# 18.net
KiCad netlist of a schematic drawn in Altium Designer
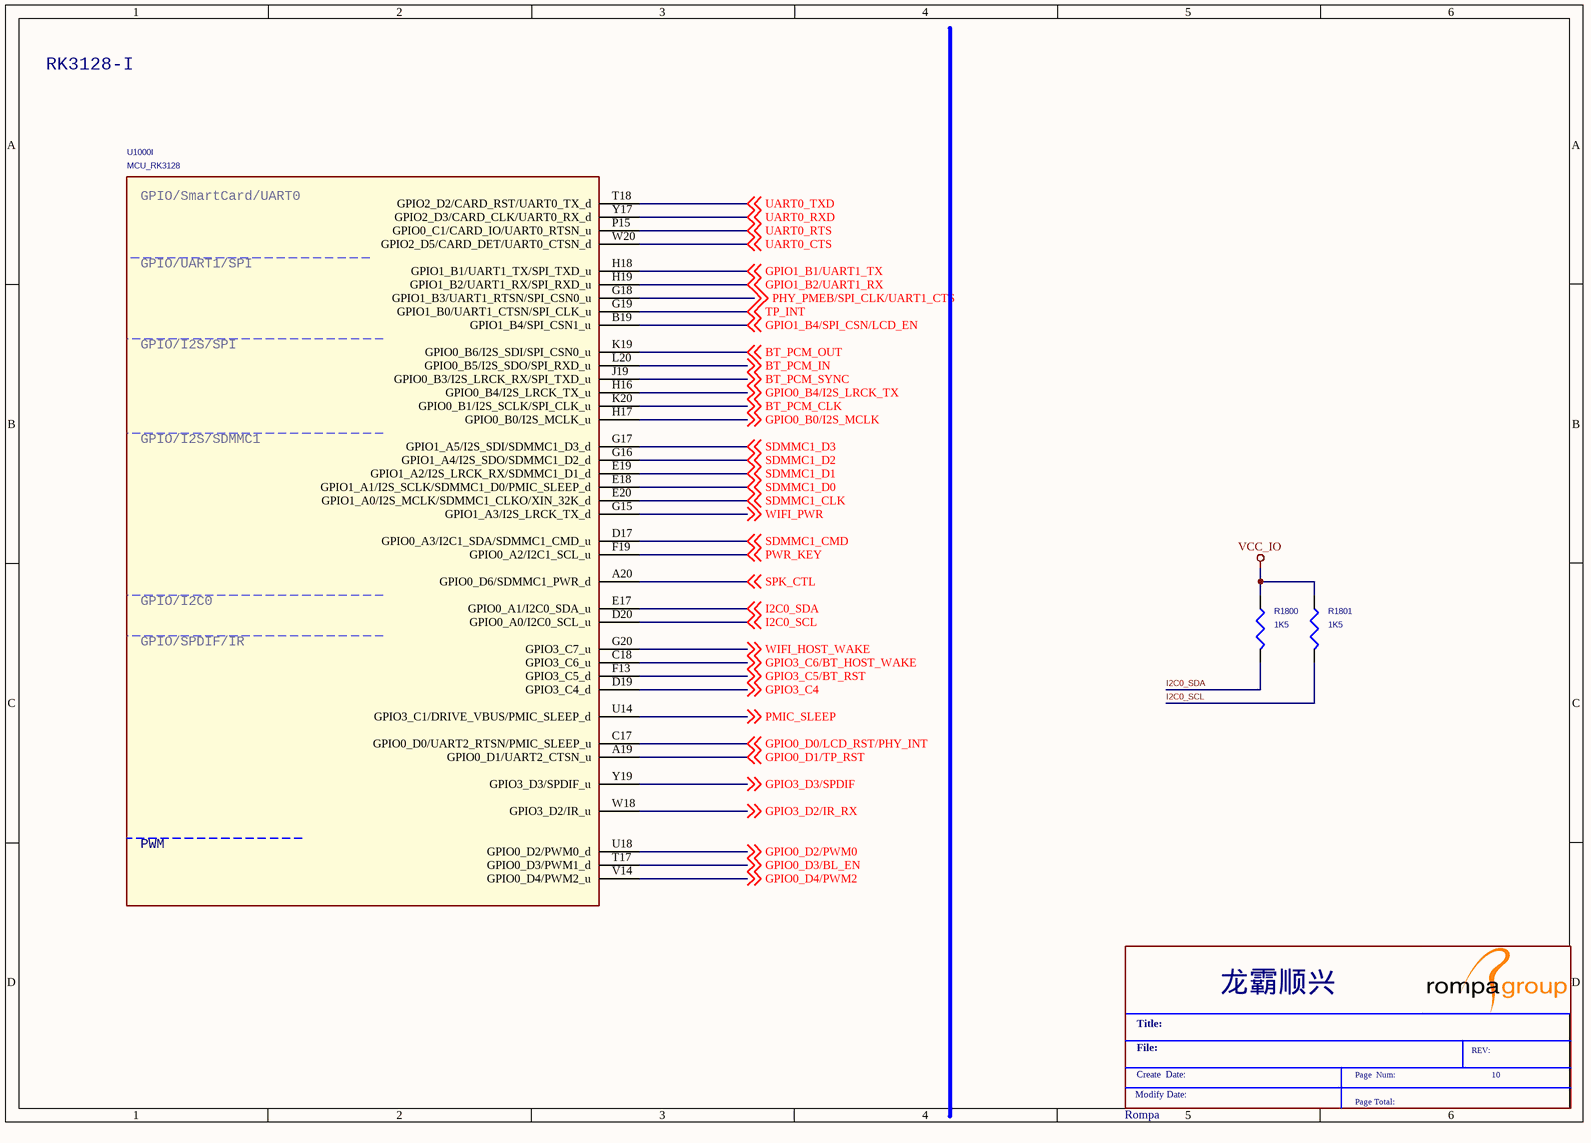
[diagram p0: 18.SchDoc]

(export (version "E")
  (design (tool "Eeschema 10.0.6"))
  (components
    (comp (ref "*")
      (value "Rompa")
      (fields (field (name "SCHEMATIC PAGE NUMBER") "10"))
      (libsource (lib "RK3128_BETA_V03_20151231_Library") (part "Rompa"))
    )
    (comp (ref "R1800")
      (value "1K5")
      (footprint "R0402")
      (description "ROHS CHIP RES 4.7K 1/16W 5%")
      (libsource (lib "*") (part "RES 1B"))
    )
    (comp (ref "R1801")
      (value "1K5")
      (footprint "R0402")
      (description "ROHS CHIP RES 4.7K 1/16W 5%")
      (libsource (lib "*") (part "RES 1B"))
    )
    (comp (ref "U1000")
      (value "MCU_RK3128")
      (footprint "BGA316-14X14-0.65")
      (libsource (lib "*") (part "MCU_RK3128"))
    )
  )
  (nets
    (net (code "1") (name "BT_PCM_CLK") (class "Default")
      (node (ref "U1000") (pin "K20") (pinfunction "GPIO0_B1/I2S_SCLK/SPI_CLK_u_K20") (pintype "passive"))
    )
    (net (code "2") (name "BT_PCM_IN") (class "Default")
      (node (ref "U1000") (pin "L20") (pinfunction "GPIO0_B5/I2S_SDO/SPI_RXD_u_L20") (pintype "passive"))
    )
    (net (code "3") (name "BT_PCM_OUT") (class "Default")
      (node (ref "U1000") (pin "K19") (pinfunction "GPIO0_B6/I2S_SDI/SPI_CSN0_u_K19") (pintype "passive"))
    )
    (net (code "4") (name "BT_PCM_SYNC") (class "Default")
      (node (ref "U1000") (pin "J19") (pinfunction "GPIO0_B3/I2S_LRCK_RX/SPI_TXD_u_J19") (pintype "passive"))
    )
    (net (code "5") (name "GPIO0_B0{slash}I2S_MCLK") (class "Default")
      (node (ref "U1000") (pin "H17") (pinfunction "GPIO0_B0/I2S_MCLK_u_H17") (pintype "passive"))
    )
    (net (code "6") (name "GPIO0_B4{slash}I2S_LRCK_TX") (class "Default")
      (node (ref "U1000") (pin "H16") (pinfunction "GPIO0_B4/I2S_LRCK_TX_u_H16") (pintype "passive"))
    )
    (net (code "7") (name "GPIO0_D0{slash}LCD_RST{slash}PHY_INT") (class "Default")
      (node (ref "U1000") (pin "C17") (pinfunction "GPIO0_D0/UART2_RTSN/PMIC_SLEEP_u_C17") (pintype "passive"))
    )
    (net (code "8") (name "GPIO0_D1{slash}TP_RST") (class "Default")
      (node (ref "U1000") (pin "A19") (pinfunction "GPIO0_D1/UART2_CTSN_u_A19") (pintype "passive"))
    )
    (net (code "9") (name "GPIO0_D2{slash}PWM0") (class "Default")
      (node (ref "U1000") (pin "U18") (pinfunction "GPIO0_D2/PWM0_d_U18") (pintype "passive"))
    )
    (net (code "10") (name "GPIO0_D3{slash}BL_EN") (class "Default")
      (node (ref "U1000") (pin "T17") (pinfunction "GPIO0_D3/PWM1_d_T17") (pintype "passive"))
    )
    (net (code "11") (name "GPIO0_D4{slash}PWM2") (class "Default")
      (node (ref "U1000") (pin "V14") (pinfunction "GPIO0_D4/PWM2_u_V14") (pintype "passive"))
    )
    (net (code "12") (name "GPIO1_B1{slash}UART1_TX") (class "Default")
      (node (ref "U1000") (pin "H18") (pinfunction "GPIO1_B1/UART1_TX/SPI_TXD_u_H18") (pintype "passive"))
    )
    (net (code "13") (name "GPIO1_B2{slash}UART1_RX") (class "Default")
      (node (ref "U1000") (pin "H19") (pinfunction "GPIO1_B2/UART1_RX/SPI_RXD_u_H19") (pintype "passive"))
    )
    (net (code "14") (name "GPIO1_B4{slash}SPI_CSN{slash}LCD_EN") (class "Default")
      (node (ref "U1000") (pin "B19") (pinfunction "GPIO1_B4/SPI_CSN1_u_B19") (pintype "passive"))
    )
    (net (code "15") (name "GPIO3_C4") (class "Default")
      (node (ref "U1000") (pin "D19") (pinfunction "GPIO3_C4_d_D19") (pintype "passive"))
    )
    (net (code "16") (name "GPIO3_C5{slash}BT_RST") (class "Default")
      (node (ref "U1000") (pin "F13") (pinfunction "GPIO3_C5_d_F13") (pintype "passive"))
    )
    (net (code "17") (name "GPIO3_C6{slash}BT_HOST_WAKE") (class "Default")
      (node (ref "U1000") (pin "C18") (pinfunction "GPIO3_C6_u_C18") (pintype "passive"))
    )
    (net (code "18") (name "GPIO3_D2{slash}IR_RX") (class "Default")
      (node (ref "U1000") (pin "W18") (pinfunction "GPIO3_D2/IR_u_W18") (pintype "passive"))
    )
    (net (code "19") (name "GPIO3_D3{slash}SPDIF") (class "Default")
      (node (ref "U1000") (pin "Y19") (pinfunction "GPIO3_D3/SPDIF_u_Y19") (pintype "passive"))
    )
    (net (code "20") (name "I2C0_SCL") (class "Default")
      (node (ref "R1801") (pin "2") (pinfunction "2_2") (pintype "passive"))
      (node (ref "U1000") (pin "D20") (pinfunction "GPIO0_A0/I2C0_SCL_u_D20") (pintype "passive"))
    )
    (net (code "21") (name "I2C0_SDA") (class "Default")
      (node (ref "R1800") (pin "2") (pinfunction "2_2") (pintype "passive"))
      (node (ref "U1000") (pin "E17") (pinfunction "GPIO0_A1/I2C0_SDA_u_E17") (pintype "passive"))
    )
    (net (code "22") (name "PHY_PMEB{slash}SPI_CLK{slash}UART1_CTS") (class "Default")
      (node (ref "U1000") (pin "G18") (pinfunction "GPIO1_B3/UART1_RTSN/SPI_CSN0_u_G18") (pintype "passive"))
    )
    (net (code "23") (name "PMIC_SLEEP") (class "Default")
      (node (ref "U1000") (pin "U14") (pinfunction "GPIO3_C1/DRIVE_VBUS/PMIC_SLEEP_d_U14") (pintype "passive"))
    )
    (net (code "24") (name "PWR_KEY") (class "Default")
      (node (ref "U1000") (pin "F19") (pinfunction "GPIO0_A2/I2C1_SCL_u_F19") (pintype "passive"))
    )
    (net (code "25") (name "SDMMC1_CLK") (class "Default")
      (node (ref "U1000") (pin "E20") (pinfunction "GPIO1_A0/I2S_MCLK/SDMMC1_CLKO/XIN_32K_d_E20") (pintype "passive"))
    )
    (net (code "26") (name "SDMMC1_CMD") (class "Default")
      (node (ref "U1000") (pin "D17") (pinfunction "GPIO0_A3/I2C1_SDA/SDMMC1_CMD_u_D17") (pintype "passive"))
    )
    (net (code "27") (name "SDMMC1_D0") (class "Default")
      (node (ref "U1000") (pin "E18") (pinfunction "GPIO1_A1/I2S_SCLK/SDMMC1_D0/PMIC_SLEEP_d_E18") (pintype "passive"))
    )
    (net (code "28") (name "SDMMC1_D1") (class "Default")
      (node (ref "U1000") (pin "E19") (pinfunction "GPIO1_A2/I2S_LRCK_RX/SDMMC1_D1_d_E19") (pintype "passive"))
    )
    (net (code "29") (name "SDMMC1_D2") (class "Default")
      (node (ref "U1000") (pin "G16") (pinfunction "GPIO1_A4/I2S_SDO/SDMMC1_D2_d_G16") (pintype "passive"))
    )
    (net (code "30") (name "SDMMC1_D3") (class "Default")
      (node (ref "U1000") (pin "G17") (pinfunction "GPIO1_A5/I2S_SDI/SDMMC1_D3_d_G17") (pintype "passive"))
    )
    (net (code "31") (name "SPK_CTL") (class "Default")
      (node (ref "U1000") (pin "A20") (pinfunction "GPIO0_D6/SDMMC1_PWR_d_A20") (pintype "passive"))
    )
    (net (code "32") (name "TP_INT") (class "Default")
      (node (ref "U1000") (pin "G19") (pinfunction "GPIO1_B0/UART1_CTSN/SPI_CLK_u_G19") (pintype "passive"))
    )
    (net (code "33") (name "UART0_CTS") (class "Default")
      (node (ref "U1000") (pin "W20") (pinfunction "GPIO2_D5/CARD_DET/UART0_CTSN_d_W20") (pintype "passive"))
    )
    (net (code "34") (name "UART0_RTS") (class "Default")
      (node (ref "U1000") (pin "P15") (pinfunction "GPIO0_C1/CARD_IO/UART0_RTSN_u_P15") (pintype "passive"))
    )
    (net (code "35") (name "UART0_RXD") (class "Default")
      (node (ref "U1000") (pin "Y17") (pinfunction "GPIO2_D3/CARD_CLK/UART0_RX_d_Y17") (pintype "passive"))
    )
    (net (code "36") (name "UART0_TXD") (class "Default")
      (node (ref "U1000") (pin "T18") (pinfunction "GPIO2_D2/CARD_RST/UART0_TX_d_T18") (pintype "passive"))
    )
    (net (code "37") (name "VCC_IO") (class "Default")
      (node (ref "R1800") (pin "1") (pinfunction "1_1") (pintype "passive"))
      (node (ref "R1801") (pin "1") (pinfunction "1_1") (pintype "passive"))
    )
    (net (code "38") (name "WIFI_HOST_WAKE") (class "Default")
      (node (ref "U1000") (pin "G20") (pinfunction "GPIO3_C7_u_G20") (pintype "passive"))
    )
    (net (code "39") (name "WIFI_PWR") (class "Default")
      (node (ref "U1000") (pin "G15") (pinfunction "GPIO1_A3/I2S_LRCK_TX_d_G15") (pintype "passive"))
    )
  )
)
